# -NEW-AQB-5-ANTON_TRANS-PWR-GALVO.net
KiCad netlist of a schematic drawn in Altium Designer
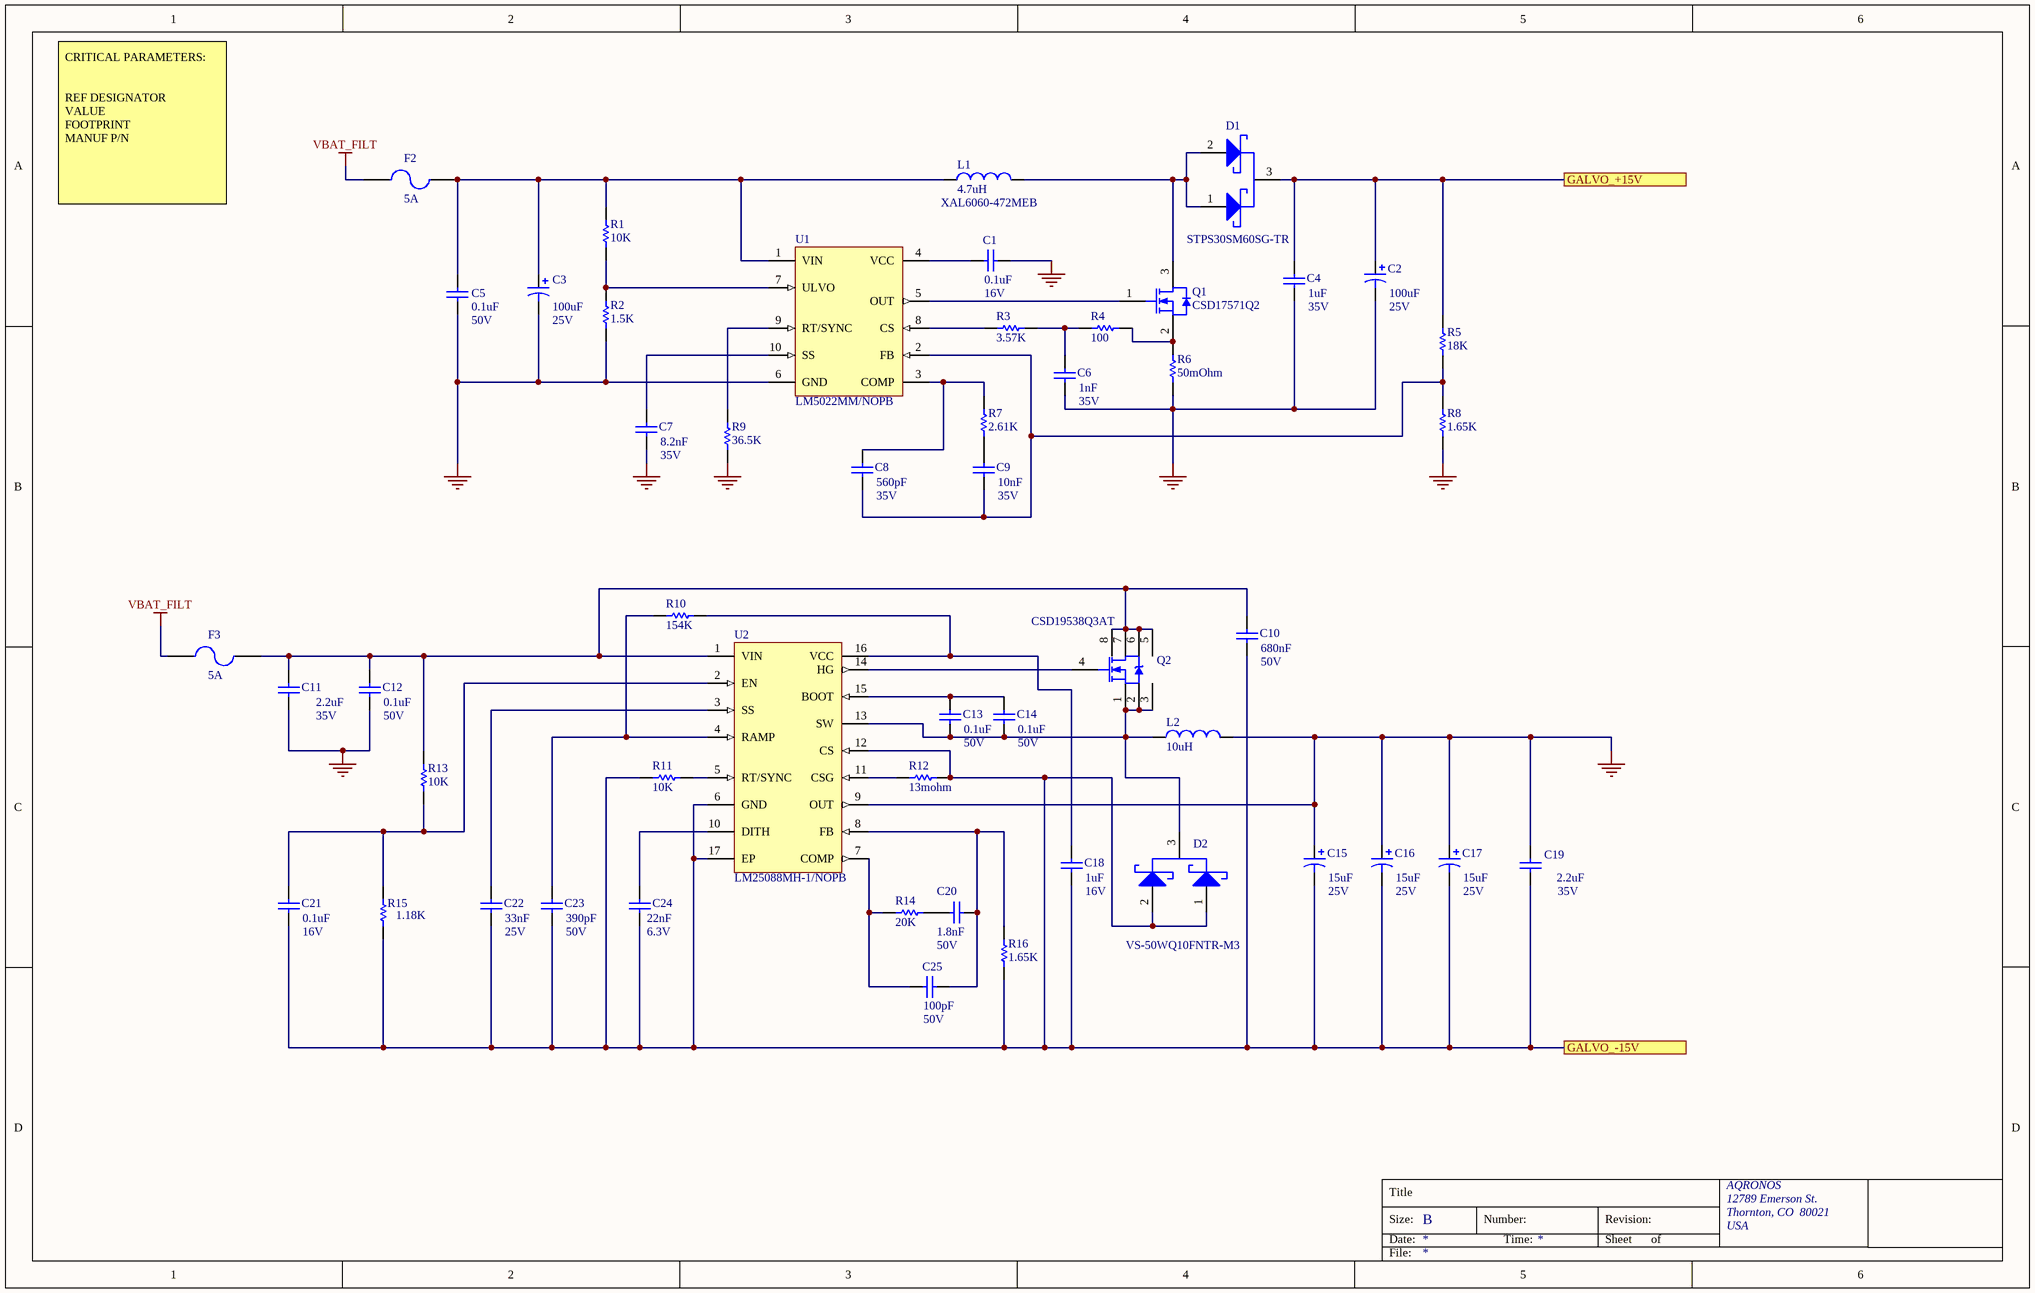
[diagram p0: -NEW-AQB-5-ANTON_TRANS-PWR-GALVO.SchDoc]

(export (version "E")
  (design (tool "Eeschema 10.0.6"))
  (components
    (comp (ref "C1")
      (value "0.1uF")
      (footprint "CAP0402")
      (description "CAP CER 0.1UF 16V X7R 0402")
      (fields
        (field (name "DISTRIBUTOR PART NUMBER") "490-3261-1-ND")
        (field (name "MANUFACTURER PART NUMBER") "GRM155R71C104KA88D")
        (field (name "VOLTAGE") "16V")
      )
      (libsource (lib "AQRONOS_TEMP_SCH") (part "Capacitor_non_pol"))
    )
    (comp (ref "C2")
      (value "100uF")
      (footprint "EEE-FK1H470XP")
      (description "CAP ALUM POLY 100UF 20% 25V SMD")
      (fields
        (field (name "DISTRIBUTOR PART NUMBER") "P123675CT-ND")
        (field (name "MANUFACTURER PART NUMBER") "25SVPF100M")
        (field (name "VOLTAGE") "25V")
      )
      (libsource (lib "AQRONOS_TEMP_SCH") (part "Capacitor-Polarized"))
    )
    (comp (ref "C3")
      (value "100uF")
      (description "CAP ALUM POLY HYB 100UF 25V SMD")
      (fields
        (field (name "DISTRIBUTOR PART NUMBER") "P15436CT-ND")
        (field (name "MANUFACTURER PART NUMBER") "EEHZA1E101XP")
        (field (name "VOLTAGE") "25V")
      )
      (libsource (lib "AQRONOS_TEMP_SCH") (part "Capacitor-Polarized"))
    )
    (comp (ref "C4")
      (value "1uF")
      (footprint "CAP0402")
      (description "CAP CER 1UF 35V X5R 0402")
      (fields
        (field (name "DISTRIBUTOR PART NUMBER") "445-9073-1-ND")
        (field (name "MANUFACTURER PART NUMBER") "C1005X5R1V105K050BC")
        (field (name "VOLTAGE") "35V")
      )
      (libsource (lib "AQRONOS_TEMP_SCH") (part "Capacitor_non_pol"))
    )
    (comp (ref "C5")
      (value "0.1uF")
      (footprint "CAP0402")
      (description "CAP CER 0.1UF 50V X5R 0402")
      (fields
        (field (name "DISTRIBUTOR PART NUMBER") "445-5942-1-ND")
        (field (name "MANUFACTURER PART NUMBER") "C1005X5R1H104K050BB")
        (field (name "VOLTAGE") "50V")
      )
      (libsource (lib "AQRONOS_TEMP_SCH") (part "Capacitor_non_pol"))
    )
    (comp (ref "C6")
      (value "1nF")
      (footprint "CAP0402")
      (description "CAP CER 1000PF 50V C0G/NP0 0402")
      (fields
        (field (name "DISTRIBUTOR PART NUMBER") "490-6190-1-ND")
        (field (name "MANUFACTURER PART NUMBER") "GRM1555C1H102JA01J")
        (field (name "VOLTAGE") "35V")
      )
      (libsource (lib "AQRONOS_TEMP_SCH") (part "Capacitor_non_pol"))
    )
    (comp (ref "C7")
      (value "8.2nF")
      (footprint "CAP0402")
      (description "CAP CER 8200PF 25V X7R 0402")
      (fields
        (field (name "DISTRIBUTOR PART NUMBER") "490-1311-1-ND")
        (field (name "MANUFACTURER PART NUMBER") "GRM155R71E822KA01D")
        (field (name "VOLTAGE") "35V")
      )
      (libsource (lib "AQRONOS_TEMP_SCH") (part "Capacitor_non_pol"))
    )
    (comp (ref "C8")
      (value "560pF")
      (footprint "CAP0402")
      (description "CAP CER 560PF 50V C0G/NP0 0402")
      (fields
        (field (name "DISTRIBUTOR PART NUMBER") "490-6248-1-ND")
        (field (name "MANUFACTURER PART NUMBER") "GRM1555C1H561JA01J")
        (field (name "VOLTAGE") "35V")
      )
      (libsource (lib "AQRONOS_TEMP_SCH") (part "Capacitor_non_pol"))
    )
    (comp (ref "C9")
      (value "10nF")
      (footprint "CAP0402")
      (description "CAP CER 10000PF 35V X7R 0402")
      (fields
        (field (name "DISTRIBUTOR PART NUMBER") "445-6900-1-ND")
        (field (name "MANUFACTURER PART NUMBER") "CGA2B3X7R1V103K050BB")
        (field (name "VOLTAGE") "35V")
      )
      (libsource (lib "AQRONOS_TEMP_SCH") (part "Capacitor_non_pol"))
    )
    (comp (ref "C10")
      (value "680nF")
      (footprint "CAP0603")
      (description "CAP CER 0.68UF 50V X5R 0603")
      (fields
        (field (name "DISTRIBUTOR PART NUMBER") "445-12509-1-ND")
        (field (name "MANUFACTURER PART NUMBER") "C1608X5R1H684K080AB")
        (field (name "VOLTAGE") "50V")
      )
      (libsource (lib "AQRONOS_TEMP_SCH") (part "Capacitor_non_pol"))
    )
    (comp (ref "C11")
      (value "2.2uF")
      (footprint "CAP0603")
      (description "CAP CER 2.2UF 35V X5R 0603")
      (fields
        (field (name "DISTRIBUTOR PART NUMBER") "445-8025-1-ND")
        (field (name "MANUFACTURER PART NUMBER") "C1608X5R1V225K080AC")
        (field (name "VOLTAGE") "35V")
      )
      (libsource (lib "AQRONOS_TEMP_SCH") (part "Capacitor_non_pol"))
    )
    (comp (ref "C12")
      (value "0.1uF")
      (footprint "CAP0805")
      (description "CAP CER 0.1UF 50V X7R 0805")
      (fields
        (field (name "DISTRIBUTOR PART NUMBER") "311-1140-1-ND")
        (field (name "MANUFACTURER PART NUMBER") "CC0805KRX7R9BB104")
        (field (name "VOLTAGE") "50V")
      )
      (libsource (lib "AQRONOS_TEMP_SCH") (part "Capacitor_non_pol"))
    )
    (comp (ref "C13")
      (value "0.1uF")
      (footprint "CAP0805")
      (description "CAP CER 0.1UF 50V X7R 0805")
      (fields
        (field (name "DISTRIBUTOR PART NUMBER") "311-1140-1-ND")
        (field (name "MANUFACTURER PART NUMBER") "CC0805KRX7R9BB104")
        (field (name "VOLTAGE") "50V")
      )
      (libsource (lib "AQRONOS_TEMP_SCH") (part "Capacitor_non_pol"))
    )
    (comp (ref "C14")
      (value "0.1uF")
      (footprint "CAP0805")
      (description "CAP CER 0.1UF 50V X7R 0805")
      (fields
        (field (name "DISTRIBUTOR PART NUMBER") "311-1140-1-ND")
        (field (name "MANUFACTURER PART NUMBER") "CC0805KRX7R9BB104")
        (field (name "VOLTAGE") "50V")
      )
      (libsource (lib "AQRONOS_TEMP_SCH") (part "Capacitor_non_pol"))
    )
    (comp (ref "C15")
      (value "15uF")
      (footprint "EEE-FK1H470XP")
      (description "CAP ALUM POLY 15UF 20% 25V SMD")
      (fields
        (field (name "DISTRIBUTOR PART NUMBER") "P18932CT-ND")
        (field (name "MANUFACTURER PART NUMBER") "25SVPG15M")
        (field (name "VOLTAGE") "25V")
      )
      (libsource (lib "AQRONOS_TEMP_SCH") (part "Capacitor-Polarized"))
    )
    (comp (ref "C16")
      (value "15uF")
      (footprint "EEE-FK1H470XP")
      (description "CAP ALUM POLY 15UF 20% 25V SMD")
      (fields
        (field (name "DISTRIBUTOR PART NUMBER") "P18932CT-ND")
        (field (name "MANUFACTURER PART NUMBER") "25SVPG15M")
        (field (name "VOLTAGE") "25V")
      )
      (libsource (lib "AQRONOS_TEMP_SCH") (part "Capacitor-Polarized"))
    )
    (comp (ref "C17")
      (value "15uF")
      (footprint "EEE-FK1H470XP")
      (description "CAP ALUM POLY 15UF 20% 25V SMD")
      (fields
        (field (name "DISTRIBUTOR PART NUMBER") "P18932CT-ND")
        (field (name "MANUFACTURER PART NUMBER") "25SVPG15M")
        (field (name "VOLTAGE") "25V")
      )
      (libsource (lib "AQRONOS_TEMP_SCH") (part "Capacitor-Polarized"))
    )
    (comp (ref "C18")
      (value "1uF")
      (footprint "CAP0603")
      (description "CAP CER 1UF 16V X7R 0603")
      (fields
        (field (name "DISTRIBUTOR PART NUMBER") "587-1241-1-ND")
        (field (name "MANUFACTURER PART NUMBER") "EMK107B7105KA-T")
        (field (name "VOLTAGE") "16V")
      )
      (libsource (lib "AQRONOS_TEMP_SCH") (part "Capacitor_non_pol"))
    )
    (comp (ref "C19")
      (value "2.2uF")
      (footprint "CAP0603")
      (description "CAP CER 2.2UF 35V X5R 0603")
      (fields
        (field (name "DISTRIBUTOR PART NUMBER") "445-8025-1-ND")
        (field (name "MANUFACTURER PART NUMBER") "C1608X5R1V225K080AC")
        (field (name "VOLTAGE") "35V")
      )
      (libsource (lib "AQRONOS_TEMP_SCH") (part "Capacitor_non_pol"))
    )
    (comp (ref "C20")
      (value "1.8nF")
      (footprint "CAP0805")
      (description "CAP CER 1800PF 50V C0G 0805")
      (fields
        (field (name "DISTRIBUTOR PART NUMBER") "445-12616-1-ND")
        (field (name "MANUFACTURER PART NUMBER") "CGA4C2C0G1H182J060AA")
        (field (name "VOLTAGE") "50V")
      )
      (libsource (lib "AQRONOS_TEMP_SCH") (part "Capacitor_non_pol"))
    )
    (comp (ref "C21")
      (value "0.1uF")
      (footprint "CAP0402")
      (description "CAP CER 0.1UF 16V X7R 0402")
      (fields
        (field (name "DISTRIBUTOR PART NUMBER") "490-3261-1-ND")
        (field (name "MANUFACTURER PART NUMBER") "GRM155R71C104KA88D")
        (field (name "VOLTAGE") "16V")
      )
      (libsource (lib "AQRONOS_TEMP_SCH") (part "Capacitor_non_pol"))
    )
    (comp (ref "C22")
      (value "33nF")
      (footprint "CAP0402")
      (description "CAP CER 0.033UF 25V X7R 0402")
      (fields
        (field (name "DISTRIBUTOR PART NUMBER") "490-3253-1-ND")
        (field (name "MANUFACTURER PART NUMBER") "GRM155R71E333KA88D")
        (field (name "VOLTAGE") "25V")
      )
      (libsource (lib "AQRONOS_TEMP_SCH") (part "Capacitor_non_pol"))
    )
    (comp (ref "C23")
      (value "390pF")
      (footprint "CAP0402")
      (description "CAP CER 390PF 50V C0G/NP0 0402")
      (fields
        (field (name "DISTRIBUTOR PART NUMBER") "490-6236-1-ND")
        (field (name "MANUFACTURER PART NUMBER") "GRM1555C1H391JA01J")
        (field (name "VOLTAGE") "50V")
      )
      (libsource (lib "AQRONOS_TEMP_SCH") (part "Capacitor_non_pol"))
    )
    (comp (ref "C24")
      (value "22nF")
      (footprint "CAP0402")
      (description "AP CER 0.022UF 6.3V X5R 0402")
      (fields
        (field (name "DISTRIBUTOR PART NUMBER") "399-3014-1-ND")
        (field (name "MANUFACTURER PART NUMBER") "C0402C223K9PACTU")
        (field (name "VOLTAGE") "6.3V")
      )
      (libsource (lib "AQRONOS_TEMP_SCH") (part "Capacitor_non_pol"))
    )
    (comp (ref "C25")
      (value "100pF")
      (footprint "CAP0805")
      (description "CAP CER 100PF 50V C0G/NP0 0805")
      (fields
        (field (name "DISTRIBUTOR PART NUMBER") "1276-1014-1-ND")
        (field (name "MANUFACTURER PART NUMBER") "CL21C101JBANNNC")
        (field (name "VOLTAGE") "50V")
      )
      (libsource (lib "AQRONOS_TEMP_SCH") (part "Capacitor_non_pol"))
    )
    (comp (ref "D1")
      (value "Schottky-3-Terminal")
      (footprint "ONSC-D2PAK-3-418AJ_A_V")
      (description "DIODE SCHOTTKY 60V 30A D2PAK")
      (fields
        (field (name "MANUFACTURER") "On Semiconductor")
        (field (name "PARTNUMBER") "SZP6SMB20AT3G")
        (field (name "MANUFACTURER PART NUMBER") "STPS30SM60SG-TR")
      )
      (libsource (lib "AQRONOS_TEMP_SCH") (part "Schottky-3-Terminal"))
    )
    (comp (ref "D2")
      (value "VS-50WQ10FNTR-M3")
      (footprint "ONSC-D2PAK-3-418AJ_A_V")
      (description "Schottky-3-Terminal")
      (fields
        (field (name "MANUFACTURER") "On Semiconductor")
        (field (name "DISTRIBUTOR PART NUMBER") "VS-50WQ10FNTR-M3CT-ND")
      )
      (libsource (lib "AQRONOS_TEMP_SCH") (part "Schottky-3-Terminal"))
    )
    (comp (ref "F2")
      (value "Fuse")
      (footprint "RES0603")
      (description "FUSE BOARD MNT 5A 32VAC/VDC 0603")
      (fields
        (field (name "MANUFACTURER PART NUMBER") "TR/0603FA5-R")
        (field (name "MANUFACTURER") "Eaton")
        (field (name "CURRENT") "5A")
        (field (name "PUBLISHER") "Altium Limited")
      )
      (libsource (lib "AQRONOS_TEMP_SCH") (part "Fuse"))
    )
    (comp (ref "F3")
      (value "Fuse")
      (footprint "RES0603")
      (description "FUSE BOARD MNT 5A 32VAC/VDC 0603")
      (fields
        (field (name "MANUFACTURER PART NUMBER") "TR/0603FA5-R")
        (field (name "MANUFACTURER") "Eaton")
        (field (name "CURRENT") "5A")
        (field (name "PUBLISHER") "Altium Limited")
      )
      (libsource (lib "AQRONOS_TEMP_SCH") (part "Fuse"))
    )
    (comp (ref "L1")
      (value "4.7uH")
      (footprint "PA4320.104NLT")
      (description "Fixed Inductors 4.7uH 20% 11A 14.40mOhms AEC-Q200")
      (fields
        (field (name "DISTRIBUTOR PART NUMBER") "994-XAL6060-472MEB")
        (field (name "MANUFACTURER PART NUMBER") "XAL6060-472MEB")
      )
      (libsource (lib "AQRONOS_TEMP_SCH") (part "Inductor"))
    )
    (comp (ref "L2")
      (value "10uH")
      (footprint "PA4320.104NLT")
      (description "FIXED IND 10UH 5A 21 MOHM SMD")
      (fields
        (field (name "DISTRIBUTOR PART NUMBER") "SRR1208-100MLCT-ND")
        (field (name "MANUFACTURER PART NUMBER") "SRR1208-100ML")
      )
      (libsource (lib "AQRONOS_TEMP_SCH") (part "Inductor"))
    )
    (comp (ref "Q1")
      (value "CSD17571Q2")
      (footprint "NXP-SOT23_N")
      (description "N-Channel Trench MOSFET, 60 V, 0.36 A, -55 to 150 degC, 3-Pin SOT23, Tape and Reel")
      (fields (field (name "MANUFACTURER") "NXP Semiconductors") (field (name "PARTNUMBER") "BSS138P,215"))
      (libsource (lib "AQRONOS_TEMP_SCH") (part "BSS138P,215"))
    )
    (comp (ref "Q2")
      (value "CSD19538Q3AT")
      (footprint "CSD18531Q5A-3D")
      (description "MOSFET N-CH 100V 15A VSONP")
      (fields
        (field (name "MANUFACTURER PART NUMBER") "CSD19538Q3A")
        (field (name "DISTRIBUTOR PART NUMBER") "296-44473-1-ND")
        (field (name "PUBLISHER") "Altium Limited")
      )
      (libsource (lib "AQRONOS_TEMP_SCH") (part "CSD18531Q5A"))
    )
    (comp (ref "R1")
      (value "10K")
      (footprint "RES0402")
      (description "RES SMD 10K OHM 0.5% 1/16W 0402")
      (fields
        (field (name "DISTRIBUTOR PART NUMBER") "P10KDECT-ND")
        (field (name "MANUFACTURER PART NUMBER") "ERA-2AED103X")
      )
      (libsource (lib "AQRONOS_TEMP_SCH") (part "Resistor"))
    )
    (comp (ref "R2")
      (value "1.5K")
      (footprint "RES0402")
      (description "RES SMD 1.5K OHM 1% 1/5W 0402")
      (fields
        (field (name "DISTRIBUTOR PART NUMBER") "541-1.50KYCT-ND")
        (field (name "MANUFACTURER PART NUMBER") "CRCW04021K50FKED")
      )
      (libsource (lib "AQRONOS_TEMP_SCH") (part "Resistor"))
    )
    (comp (ref "R3")
      (value "3.57K")
      (footprint "RES0402")
      (description "RES SMD 3.57K OHM 1% 1/16W 0402")
      (fields
        (field (name "DISTRIBUTOR PART NUMBER") "541-3.57KLCT-ND")
        (field (name "MANUFACTURER PART NUMBER") "CRCW04023K57FKED")
      )
      (libsource (lib "AQRONOS_TEMP_SCH") (part "Resistor"))
    )
    (comp (ref "R4")
      (value "100")
      (footprint "RES0402")
      (description "RES SMD 100 OHM 1% 1/16W 0402")
      (fields
        (field (name "DISTRIBUTOR PART NUMBER") "541-100LCT-ND")
        (field (name "MANUFACTURER PART NUMBER") "CRCW0402100RFKED")
      )
      (libsource (lib "AQRONOS_TEMP_SCH") (part "Resistor"))
    )
    (comp (ref "R5")
      (value "18K")
      (footprint "RES0603")
      (description "RES SMD 18K OHM 1% 1/10W 0603")
      (fields
        (field (name "DISTRIBUTOR PART NUMBER") "311-18.0KHRCT-ND")
        (field (name "MANUFACTURER PART NUMBER") "RC0603FR-0718KL")
      )
      (libsource (lib "AQRONOS_TEMP_SCH") (part "Resistor"))
    )
    (comp (ref "R6")
      (value "50mOhm")
      (footprint "RES1206")
      (description "RES 0.05 OHM 1% 1/2W 1206")
      (fields
        (field (name "DISTRIBUTOR PART NUMBER") "CSR1206FK50L0CT-ND")
        (field (name "MANUFACTURER PART NUMBER") "CSR1206FK50L0")
      )
      (libsource (lib "AQRONOS_TEMP_SCH") (part "Resistor"))
    )
    (comp (ref "R7")
      (value "2.61K")
      (footprint "RES0402")
      (description "RES SMD 2.61K OHM 1% 1/16W 0402")
      (fields
        (field (name "DISTRIBUTOR PART NUMBER") "541-2.61KLCT-ND")
        (field (name "MANUFACTURER PART NUMBER") "CRCW04022K61FKED")
      )
      (libsource (lib "AQRONOS_TEMP_SCH") (part "Resistor"))
    )
    (comp (ref "R8")
      (value "1.65K")
      (footprint "RES0402")
      (description "RES SMD 1.65K OHM 1% 1/16W 0402")
      (fields
        (field (name "DISTRIBUTOR PART NUMBER") "541-1.65KLCT-ND")
        (field (name "MANUFACTURER PART NUMBER") "RCW04021K65FKED")
      )
      (libsource (lib "AQRONOS_TEMP_SCH") (part "Resistor"))
    )
    (comp (ref "R9")
      (value "36.5K")
      (footprint "RES0402")
      (description "RES SMD 36.5KOHM 0.1% 1/16W 0402")
      (fields
        (field (name "DISTRIBUTOR PART NUMBER") "P36.5KDCCT-ND")
        (field (name "MANUFACTURER PART NUMBER") "ERA-2AEB3652X")
      )
      (libsource (lib "AQRONOS_TEMP_SCH") (part "Resistor"))
    )
    (comp (ref "R10")
      (value "154K")
      (footprint "RES0402")
      (fields
        (field (name "DISTRIBUTOR PART NUMBER") "541-154KLCT-ND")
        (field (name "MANUFACTURER PART NUMBER") "CRCW0402154KFKED")
        (field (name "Comment") "Resistor")
      )
      (libsource (lib "AQRONOS_TEMP_SCH") (part "Resistor"))
    )
    (comp (ref "R11")
      (value "10K")
      (footprint "RES0402")
      (fields
        (field (name "DISTRIBUTOR PART NUMBER") "311-10.0KMCT-ND")
        (field (name "MANUFACTURER PART NUMBER") "RC0201FR-0710KL")
        (field (name "Comment") "Resistor")
      )
      (libsource (lib "AQRONOS_TEMP_SCH") (part "Resistor"))
    )
    (comp (ref "R12")
      (value "13mohm")
      (footprint "RES0402")
      (fields
        (field (name "DISTRIBUTOR PART NUMBER") "PRL1632.013FCT-ND")
        (field (name "MANUFACTURER PART NUMBER") "PRL1632-R013-F-T1")
        (field (name "Comment") "Resistor")
      )
      (libsource (lib "AQRONOS_TEMP_SCH") (part "Resistor"))
    )
    (comp (ref "R13")
      (value "10K")
      (footprint "RES0402")
      (fields
        (field (name "DISTRIBUTOR PART NUMBER") "311-10.0KMCT-ND")
        (field (name "MANUFACTURER PART NUMBER") "RC0201FR-0710KL")
        (field (name "Comment") "Resistor")
      )
      (libsource (lib "AQRONOS_TEMP_SCH") (part "Resistor"))
    )
    (comp (ref "R14")
      (value "20K")
      (footprint "RES0402")
      (description "RES SMD 1.65K OHM 1% 1/16W 0402")
      (fields
        (field (name "DISTRIBUTOR PART NUMBER") "541-1.65KLCT-ND")
        (field (name "MANUFACTURER PART NUMBER") "CRCW040220K0FKED")
      )
      (libsource (lib "AQRONOS_TEMP_SCH") (part "Resistor"))
    )
    (comp (ref "R15")
      (value "1.18K")
      (footprint "RES0402")
      (fields
        (field (name "DISTRIBUTOR PART NUMBER") "541-1.18KLCT-ND")
        (field (name "MANUFACTURER PART NUMBER") "CRCW04021K18FKED")
        (field (name "Comment") "Resistor")
      )
      (libsource (lib "AQRONOS_TEMP_SCH") (part "Resistor"))
    )
    (comp (ref "R16")
      (value "1.65K")
      (footprint "RES0402")
      (description "RES SMD 1.65K OHM 1% 1/16W 0402")
      (fields
        (field (name "DISTRIBUTOR PART NUMBER") "541-1.65KLCT-ND")
        (field (name "MANUFACTURER PART NUMBER") "RCW04021K65FKED")
      )
      (libsource (lib "AQRONOS_TEMP_SCH") (part "Resistor"))
    )
    (comp (ref "U1")
      (value "LM5022MM/NOPB")
      (footprint "MUB10A_N")
      (description "60V Low Side Controller for Boost and SEPIC, 10-pin MSOP, Pb-Free")
      (fields
        (field (name "MANUFACTURER") "National Semiconductor")
        (field (name "DISTRIBUTOR PART NUMBER") "LM5022MM/NOPBCT-ND")
      )
      (libsource (lib "Switcher") (part "LM5022MM/NOPB"))
    )
    (comp (ref "U2")
      (value "LM25088MH-1/NOPB")
      (footprint "MXA16A_N")
      (description "Wide Input Range Non-Synchronous Buck Controller, 16-pin TSSOP-EP, Pb-Free")
      (fields
        (field (name "MANUFACTURER") "National Semiconductor")
        (field (name "DISTRIBUTOR PART NUMBER") "LM25088MH-1/NOPB-ND")
      )
      (libsource (lib "AQRONOS_TEMP_SCH") (part "LM25088MH-1/NOPB"))
    )
  )
  (nets
    (net (code "1") (name "/GALVO_+15V") (class "Default")
      (node (ref "C2") (pin "1") (pinfunction "1_1") (pintype "passive"))
      (node (ref "C4") (pin "1") (pinfunction "1_1") (pintype "passive"))
      (node (ref "D1") (pin "3") (pinfunction "K_3") (pintype "passive"))
      (node (ref "R5") (pin "1") (pinfunction "1_1") (pintype "passive"))
    )
    (net (code "2") (name "/GALVO_-15V") (class "Default")
      (node (ref "C10") (pin "2") (pinfunction "2_2") (pintype "passive"))
      (node (ref "C15") (pin "2") (pinfunction "2_2") (pintype "passive"))
      (node (ref "C16") (pin "2") (pinfunction "2_2") (pintype "passive"))
      (node (ref "C17") (pin "2") (pinfunction "2_2") (pintype "passive"))
      (node (ref "C18") (pin "2") (pinfunction "2_2") (pintype "passive"))
      (node (ref "C19") (pin "2") (pinfunction "2_2") (pintype "passive"))
      (node (ref "C21") (pin "2") (pinfunction "2_2") (pintype "passive"))
      (node (ref "C22") (pin "2") (pinfunction "2_2") (pintype "passive"))
      (node (ref "C23") (pin "2") (pinfunction "2_2") (pintype "passive"))
      (node (ref "C24") (pin "2") (pinfunction "2_2") (pintype "passive"))
      (node (ref "D2") (pin "1") (pinfunction "A_1") (pintype "passive"))
      (node (ref "D2") (pin "2") (pinfunction "A_2") (pintype "passive"))
      (node (ref "R11") (pin "2") (pinfunction "2_2") (pintype "passive"))
      (node (ref "R12") (pin "2") (pinfunction "2_2") (pintype "passive"))
      (node (ref "R15") (pin "1") (pinfunction "1_1") (pintype "passive"))
      (node (ref "R16") (pin "1") (pinfunction "1_1") (pintype "passive"))
      (node (ref "U2") (pin "12") (pinfunction "CS_12") (pintype "input"))
      (node (ref "U2") (pin "17") (pinfunction "EP_17") (pintype "power_in"))
      (node (ref "U2") (pin "6") (pinfunction "GND_6") (pintype "power_in"))
    )
    (net (code "3") (name "GND") (class "Default")
      (node (ref "C1") (pin "2") (pinfunction "2_2") (pintype "passive"))
      (node (ref "C11") (pin "2") (pinfunction "2_2") (pintype "passive"))
      (node (ref "C12") (pin "1") (pinfunction "1_1") (pintype "passive"))
      (node (ref "C15") (pin "1") (pinfunction "1_1") (pintype "passive"))
      (node (ref "C16") (pin "1") (pinfunction "1_1") (pintype "passive"))
      (node (ref "C17") (pin "1") (pinfunction "1_1") (pintype "passive"))
      (node (ref "C19") (pin "1") (pinfunction "1_1") (pintype "passive"))
      (node (ref "C2") (pin "2") (pinfunction "2_2") (pintype "passive"))
      (node (ref "C3") (pin "2") (pinfunction "2_2") (pintype "passive"))
      (node (ref "C4") (pin "2") (pinfunction "2_2") (pintype "passive"))
      (node (ref "C5") (pin "2") (pinfunction "2_2") (pintype "passive"))
      (node (ref "C6") (pin "2") (pinfunction "2_2") (pintype "passive"))
      (node (ref "C7") (pin "2") (pinfunction "2_2") (pintype "passive"))
      (node (ref "L2") (pin "2") (pinfunction "2_2") (pintype "passive"))
      (node (ref "R2") (pin "2") (pinfunction "2_2") (pintype "passive"))
      (node (ref "R6") (pin "1") (pinfunction "1_1") (pintype "passive"))
      (node (ref "R8") (pin "1") (pinfunction "1_1") (pintype "passive"))
      (node (ref "R9") (pin "2") (pinfunction "2_2") (pintype "passive"))
      (node (ref "U1") (pin "6") (pinfunction "GND_6") (pintype "power_in"))
      (node (ref "U2") (pin "9") (pinfunction "OUT_9") (pintype "output"))
    )
    (net (code "4") (name "Net-(C6-Pad1)") (class "Default")
      (node (ref "C6") (pin "1") (pinfunction "1_1") (pintype "passive"))
      (node (ref "R3") (pin "2") (pinfunction "2_2") (pintype "passive"))
      (node (ref "R4") (pin "1") (pinfunction "1_1") (pintype "passive"))
    )
    (net (code "5") (name "Net-(C9-Pad2)") (class "Default")
      (node (ref "C9") (pin "2") (pinfunction "2_2") (pintype "passive"))
      (node (ref "R7") (pin "1") (pinfunction "1_1") (pintype "passive"))
    )
    (net (code "6") (name "Net-(C20-Pad1)") (class "Default")
      (node (ref "C20") (pin "1") (pinfunction "1_1") (pintype "passive"))
      (node (ref "R14") (pin "1") (pinfunction "1_1") (pintype "passive"))
    )
    (net (code "7") (name "Net-(D2-K)") (class "Default")
      (node (ref "C13") (pin "1") (pinfunction "1_1") (pintype "passive"))
      (node (ref "C14") (pin "1") (pinfunction "1_1") (pintype "passive"))
      (node (ref "D2") (pin "3") (pinfunction "K_3") (pintype "passive"))
      (node (ref "L2") (pin "1") (pinfunction "1_1") (pintype "passive"))
      (node (ref "Q2") (pin "1") (pinfunction "S_1") (pintype "passive"))
      (node (ref "Q2") (pin "2") (pinfunction "S_2") (pintype "passive"))
      (node (ref "Q2") (pin "3") (pinfunction "S_3") (pintype "passive"))
      (node (ref "U2") (pin "13") (pinfunction "SW_13") (pintype "passive"))
    )
    (net (code "8") (name "Net-(Q1-D)") (class "Default")
      (node (ref "D1") (pin "1") (pinfunction "A_1") (pintype "passive"))
      (node (ref "D1") (pin "2") (pinfunction "A_2") (pintype "passive"))
      (node (ref "L1") (pin "2") (pinfunction "2_2") (pintype "passive"))
      (node (ref "Q1") (pin "3") (pinfunction "D_3") (pintype "passive"))
    )
    (net (code "9") (name "Net-(Q1-G)") (class "Default")
      (node (ref "Q1") (pin "1") (pinfunction "G_1") (pintype "passive"))
      (node (ref "U1") (pin "5") (pinfunction "OUT_5") (pintype "output"))
    )
    (net (code "10") (name "Net-(Q1-S)") (class "Default")
      (node (ref "Q1") (pin "2") (pinfunction "S_2") (pintype "passive"))
      (node (ref "R4") (pin "2") (pinfunction "2_2") (pintype "passive"))
      (node (ref "R6") (pin "2") (pinfunction "2_2") (pintype "passive"))
    )
    (net (code "11") (name "Net-(Q2-G)") (class "Default")
      (node (ref "Q2") (pin "4") (pinfunction "G_4") (pintype "passive"))
      (node (ref "U2") (pin "14") (pinfunction "HG_14") (pintype "output"))
    )
    (net (code "12") (name "Net-(U1-COMP)") (class "Default")
      (node (ref "C8") (pin "2") (pinfunction "2_2") (pintype "passive"))
      (node (ref "R7") (pin "2") (pinfunction "2_2") (pintype "passive"))
      (node (ref "U1") (pin "3") (pinfunction "COMP_3") (pintype "passive"))
    )
    (net (code "13") (name "Net-(U1-CS)") (class "Default")
      (node (ref "R3") (pin "1") (pinfunction "1_1") (pintype "passive"))
      (node (ref "U1") (pin "8") (pinfunction "CS_8") (pintype "input"))
    )
    (net (code "14") (name "Net-(U1-FB)") (class "Default")
      (node (ref "C8") (pin "1") (pinfunction "1_1") (pintype "passive"))
      (node (ref "C9") (pin "1") (pinfunction "1_1") (pintype "passive"))
      (node (ref "R5") (pin "2") (pinfunction "2_2") (pintype "passive"))
      (node (ref "R8") (pin "2") (pinfunction "2_2") (pintype "passive"))
      (node (ref "U1") (pin "2") (pinfunction "FB_2") (pintype "input"))
    )
    (net (code "15") (name "Net-(U1-RT{slash}SYNC)") (class "Default")
      (node (ref "R9") (pin "1") (pinfunction "1_1") (pintype "passive"))
      (node (ref "U1") (pin "9") (pinfunction "RT/SYNC_9") (pintype "input"))
    )
    (net (code "16") (name "Net-(U1-SS)") (class "Default")
      (node (ref "C7") (pin "1") (pinfunction "1_1") (pintype "passive"))
      (node (ref "U1") (pin "10") (pinfunction "SS_10") (pintype "input"))
    )
    (net (code "17") (name "Net-(U1-ULVO)") (class "Default")
      (node (ref "R1") (pin "2") (pinfunction "2_2") (pintype "passive"))
      (node (ref "R2") (pin "1") (pinfunction "1_1") (pintype "passive"))
      (node (ref "U1") (pin "7") (pinfunction "ULVO_7") (pintype "input"))
    )
    (net (code "18") (name "Net-(U1-VCC)") (class "Default")
      (node (ref "C1") (pin "1") (pinfunction "1_1") (pintype "passive"))
      (node (ref "U1") (pin "4") (pinfunction "VCC_4") (pintype "power_in"))
    )
    (net (code "19") (name "Net-(U1-VIN)") (class "Default")
      (node (ref "C3") (pin "1") (pinfunction "1_1") (pintype "passive"))
      (node (ref "C5") (pin "1") (pinfunction "1_1") (pintype "passive"))
      (node (ref "F2") (pin "2") (pinfunction "2_2") (pintype "passive"))
      (node (ref "L1") (pin "1") (pinfunction "1_1") (pintype "passive"))
      (node (ref "R1") (pin "1") (pinfunction "1_1") (pintype "passive"))
      (node (ref "U1") (pin "1") (pinfunction "VIN_1") (pintype "power_in"))
    )
    (net (code "20") (name "Net-(U2-BOOT)") (class "Default")
      (node (ref "C13") (pin "2") (pinfunction "2_2") (pintype "passive"))
      (node (ref "C14") (pin "2") (pinfunction "2_2") (pintype "passive"))
      (node (ref "U2") (pin "15") (pinfunction "BOOT_15") (pintype "input"))
    )
    (net (code "21") (name "Net-(U2-COMP)") (class "Default")
      (node (ref "C25") (pin "1") (pinfunction "1_1") (pintype "passive"))
      (node (ref "R14") (pin "2") (pinfunction "2_2") (pintype "passive"))
      (node (ref "U2") (pin "7") (pinfunction "COMP_7") (pintype "output"))
    )
    (net (code "22") (name "Net-(U2-CSG)") (class "Default")
      (node (ref "R12") (pin "1") (pinfunction "1_1") (pintype "passive"))
      (node (ref "U2") (pin "11") (pinfunction "CSG_11") (pintype "input"))
    )
    (net (code "23") (name "Net-(U2-DITH)") (class "Default")
      (node (ref "C24") (pin "1") (pinfunction "1_1") (pintype "passive"))
      (node (ref "U2") (pin "10") (pinfunction "DITH_10") (pintype "power_in"))
    )
    (net (code "24") (name "Net-(U2-EN)") (class "Default")
      (node (ref "C21") (pin "1") (pinfunction "1_1") (pintype "passive"))
      (node (ref "R13") (pin "1") (pinfunction "1_1") (pintype "passive"))
      (node (ref "R15") (pin "2") (pinfunction "2_2") (pintype "passive"))
      (node (ref "U2") (pin "2") (pinfunction "EN_2") (pintype "input"))
    )
    (net (code "25") (name "Net-(U2-FB)") (class "Default")
      (node (ref "C20") (pin "2") (pinfunction "2_2") (pintype "passive"))
      (node (ref "C25") (pin "2") (pinfunction "2_2") (pintype "passive"))
      (node (ref "R16") (pin "2") (pinfunction "2_2") (pintype "passive"))
      (node (ref "U2") (pin "8") (pinfunction "FB_8") (pintype "input"))
    )
    (net (code "26") (name "Net-(U2-RAMP)") (class "Default")
      (node (ref "C23") (pin "1") (pinfunction "1_1") (pintype "passive"))
      (node (ref "R10") (pin "2") (pinfunction "2_2") (pintype "passive"))
      (node (ref "U2") (pin "4") (pinfunction "RAMP_4") (pintype "input"))
    )
    (net (code "27") (name "Net-(U2-RT{slash}SYNC)") (class "Default")
      (node (ref "R11") (pin "1") (pinfunction "1_1") (pintype "passive"))
      (node (ref "U2") (pin "5") (pinfunction "RT/SYNC_5") (pintype "input"))
    )
    (net (code "28") (name "Net-(U2-SS)") (class "Default")
      (node (ref "C22") (pin "1") (pinfunction "1_1") (pintype "passive"))
      (node (ref "U2") (pin "3") (pinfunction "SS_3") (pintype "input"))
    )
    (net (code "29") (name "Net-(U2-VCC)") (class "Default")
      (node (ref "C18") (pin "1") (pinfunction "1_1") (pintype "passive"))
      (node (ref "R10") (pin "1") (pinfunction "1_1") (pintype "passive"))
      (node (ref "U2") (pin "16") (pinfunction "VCC_16") (pintype "power_in"))
    )
    (net (code "30") (name "Net-(U2-VIN)") (class "Default")
      (node (ref "C10") (pin "1") (pinfunction "1_1") (pintype "passive"))
      (node (ref "C11") (pin "1") (pinfunction "1_1") (pintype "passive"))
      (node (ref "C12") (pin "2") (pinfunction "2_2") (pintype "passive"))
      (node (ref "F3") (pin "2") (pinfunction "2_2") (pintype "passive"))
      (node (ref "Q2") (pin "5") (pinfunction "D_5") (pintype "passive"))
      (node (ref "Q2") (pin "6") (pinfunction "D_6") (pintype "passive"))
      (node (ref "Q2") (pin "7") (pinfunction "D_7") (pintype "passive"))
      (node (ref "Q2") (pin "8") (pinfunction "D_8") (pintype "passive"))
      (node (ref "R13") (pin "2") (pinfunction "2_2") (pintype "passive"))
      (node (ref "U2") (pin "1") (pinfunction "VIN_1") (pintype "power_in"))
    )
    (net (code "31") (name "VBAT_FILT") (class "Default")
      (node (ref "F2") (pin "1") (pinfunction "1_1") (pintype "passive"))
      (node (ref "F3") (pin "1") (pinfunction "1_1") (pintype "passive"))
    )
  )
)
